# Leds.net
KiCad netlist of a schematic drawn in Altium Designer
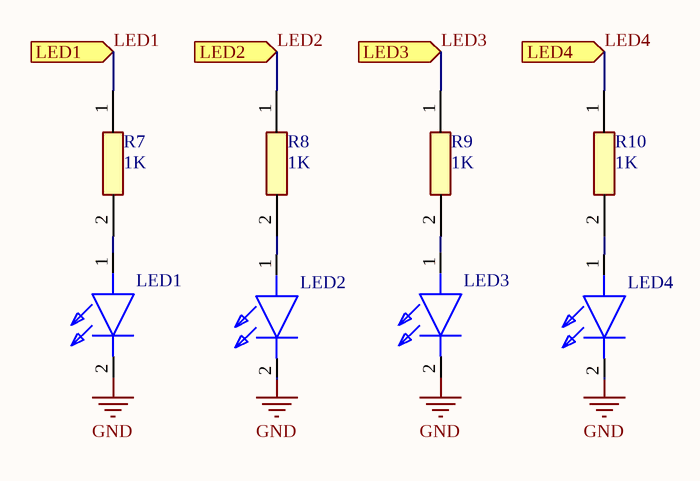
[diagram p0: Leds.SchDoc]

(export (version "E")
  (design (tool "Eeschema 10.0.6"))
  (components
    (comp (ref "LED1")
      (value "APHCM2012SURCK-F01")
      (footprint "SamacSys:APHCM2012SURCKF01")
      (description "LED")
      (fields (field (name "MOUSER PART NUMBER") "604-APHCM2012SURCK"))
      (libsource (lib "*") (part "APHCM2012SURCK-F01"))
    )
    (comp (ref "LED2")
      (value "APHCM2012SURCK-F01")
      (footprint "SamacSys:APHCM2012SURCKF01")
      (description "LED")
      (fields (field (name "MOUSER PART NUMBER") "604-APHCM2012SURCK"))
      (libsource (lib "*") (part "APHCM2012SURCK-F01"))
    )
    (comp (ref "LED3")
      (value "APHCM2012SURCK-F01")
      (footprint "SamacSys:APHCM2012SURCKF01")
      (description "LED")
      (fields (field (name "MOUSER PART NUMBER") "604-APHCM2012SURCK"))
      (libsource (lib "*") (part "APHCM2012SURCK-F01"))
    )
    (comp (ref "LED4")
      (value "APHCM2012SURCK-F01")
      (footprint "SamacSys:APHCM2012SURCKF01")
      (description "LED")
      (fields (field (name "MOUSER PART NUMBER") "604-APHCM2012SURCK"))
      (libsource (lib "*") (part "APHCM2012SURCK-F01"))
    )
    (comp (ref "R7")
      (value "1K")
      (footprint "SamacSys:RESC3216X75N")
      (description "Resistor")
      (fields
        (field (name "MANUFACTURER_PART_NUMBER") "CR1206-F/-2R00ELF")
        (field (name "MOUSER PART NUMBER") "652-CR1206-F/2R00ELF")
      )
      (libsource (lib "*") (part "CR1206-F_-2R00ELF"))
    )
    (comp (ref "R8")
      (value "1K")
      (footprint "SamacSys:RESC3216X75N")
      (description "Resistor")
      (fields
        (field (name "MANUFACTURER_PART_NUMBER") "CR1206-F/-2R00ELF")
        (field (name "MOUSER PART NUMBER") "652-CR1206-F/2R00ELF")
      )
      (libsource (lib "*") (part "CR1206-F_-2R00ELF"))
    )
    (comp (ref "R9")
      (value "1K")
      (footprint "SamacSys:RESC3216X75N")
      (description "Resistor")
      (fields
        (field (name "MANUFACTURER_PART_NUMBER") "CR1206-F/-2R00ELF")
        (field (name "MOUSER PART NUMBER") "652-CR1206-F/2R00ELF")
      )
      (libsource (lib "*") (part "CR1206-F_-2R00ELF"))
    )
    (comp (ref "R10")
      (value "1K")
      (footprint "SamacSys:RESC3216X75N")
      (description "Resistor")
      (fields
        (field (name "MANUFACTURER_PART_NUMBER") "CR1206-F/-2R00ELF")
        (field (name "MOUSER PART NUMBER") "652-CR1206-F/2R00ELF")
      )
      (libsource (lib "*") (part "CR1206-F_-2R00ELF"))
    )
  )
  (nets
    (net (code "1") (name "/LED1") (class "Default")
      (node (ref "R7") (pin "1") (pinfunction "1_1") (pintype "passive"))
    )
    (net (code "2") (name "/LED2") (class "Default")
      (node (ref "R8") (pin "1") (pinfunction "1_1") (pintype "passive"))
    )
    (net (code "3") (name "/LED3") (class "Default")
      (node (ref "R9") (pin "1") (pinfunction "1_1") (pintype "passive"))
    )
    (net (code "4") (name "/LED4") (class "Default")
      (node (ref "R10") (pin "1") (pinfunction "1_1") (pintype "passive"))
    )
    (net (code "5") (name "GND") (class "Default")
      (node (ref "LED1") (pin "2") (pinfunction "K_2") (pintype "passive"))
      (node (ref "LED2") (pin "2") (pinfunction "K_2") (pintype "passive"))
      (node (ref "LED3") (pin "2") (pinfunction "K_2") (pintype "passive"))
      (node (ref "LED4") (pin "2") (pinfunction "K_2") (pintype "passive"))
    )
    (net (code "6") (name "Net-(LED1-A)") (class "Default")
      (node (ref "LED1") (pin "1") (pinfunction "A_1") (pintype "passive"))
      (node (ref "R7") (pin "2") (pinfunction "2_2") (pintype "passive"))
    )
    (net (code "7") (name "Net-(LED2-A)") (class "Default")
      (node (ref "LED2") (pin "1") (pinfunction "A_1") (pintype "passive"))
      (node (ref "R8") (pin "2") (pinfunction "2_2") (pintype "passive"))
    )
    (net (code "8") (name "Net-(LED3-A)") (class "Default")
      (node (ref "LED3") (pin "1") (pinfunction "A_1") (pintype "passive"))
      (node (ref "R9") (pin "2") (pinfunction "2_2") (pintype "passive"))
    )
    (net (code "9") (name "Net-(LED4-A)") (class "Default")
      (node (ref "LED4") (pin "1") (pinfunction "A_1") (pintype "passive"))
      (node (ref "R10") (pin "2") (pinfunction "2_2") (pintype "passive"))
    )
  )
)
